# Motor-Driver-Sheet.net
KiCad netlist of a schematic drawn in Altium Designer
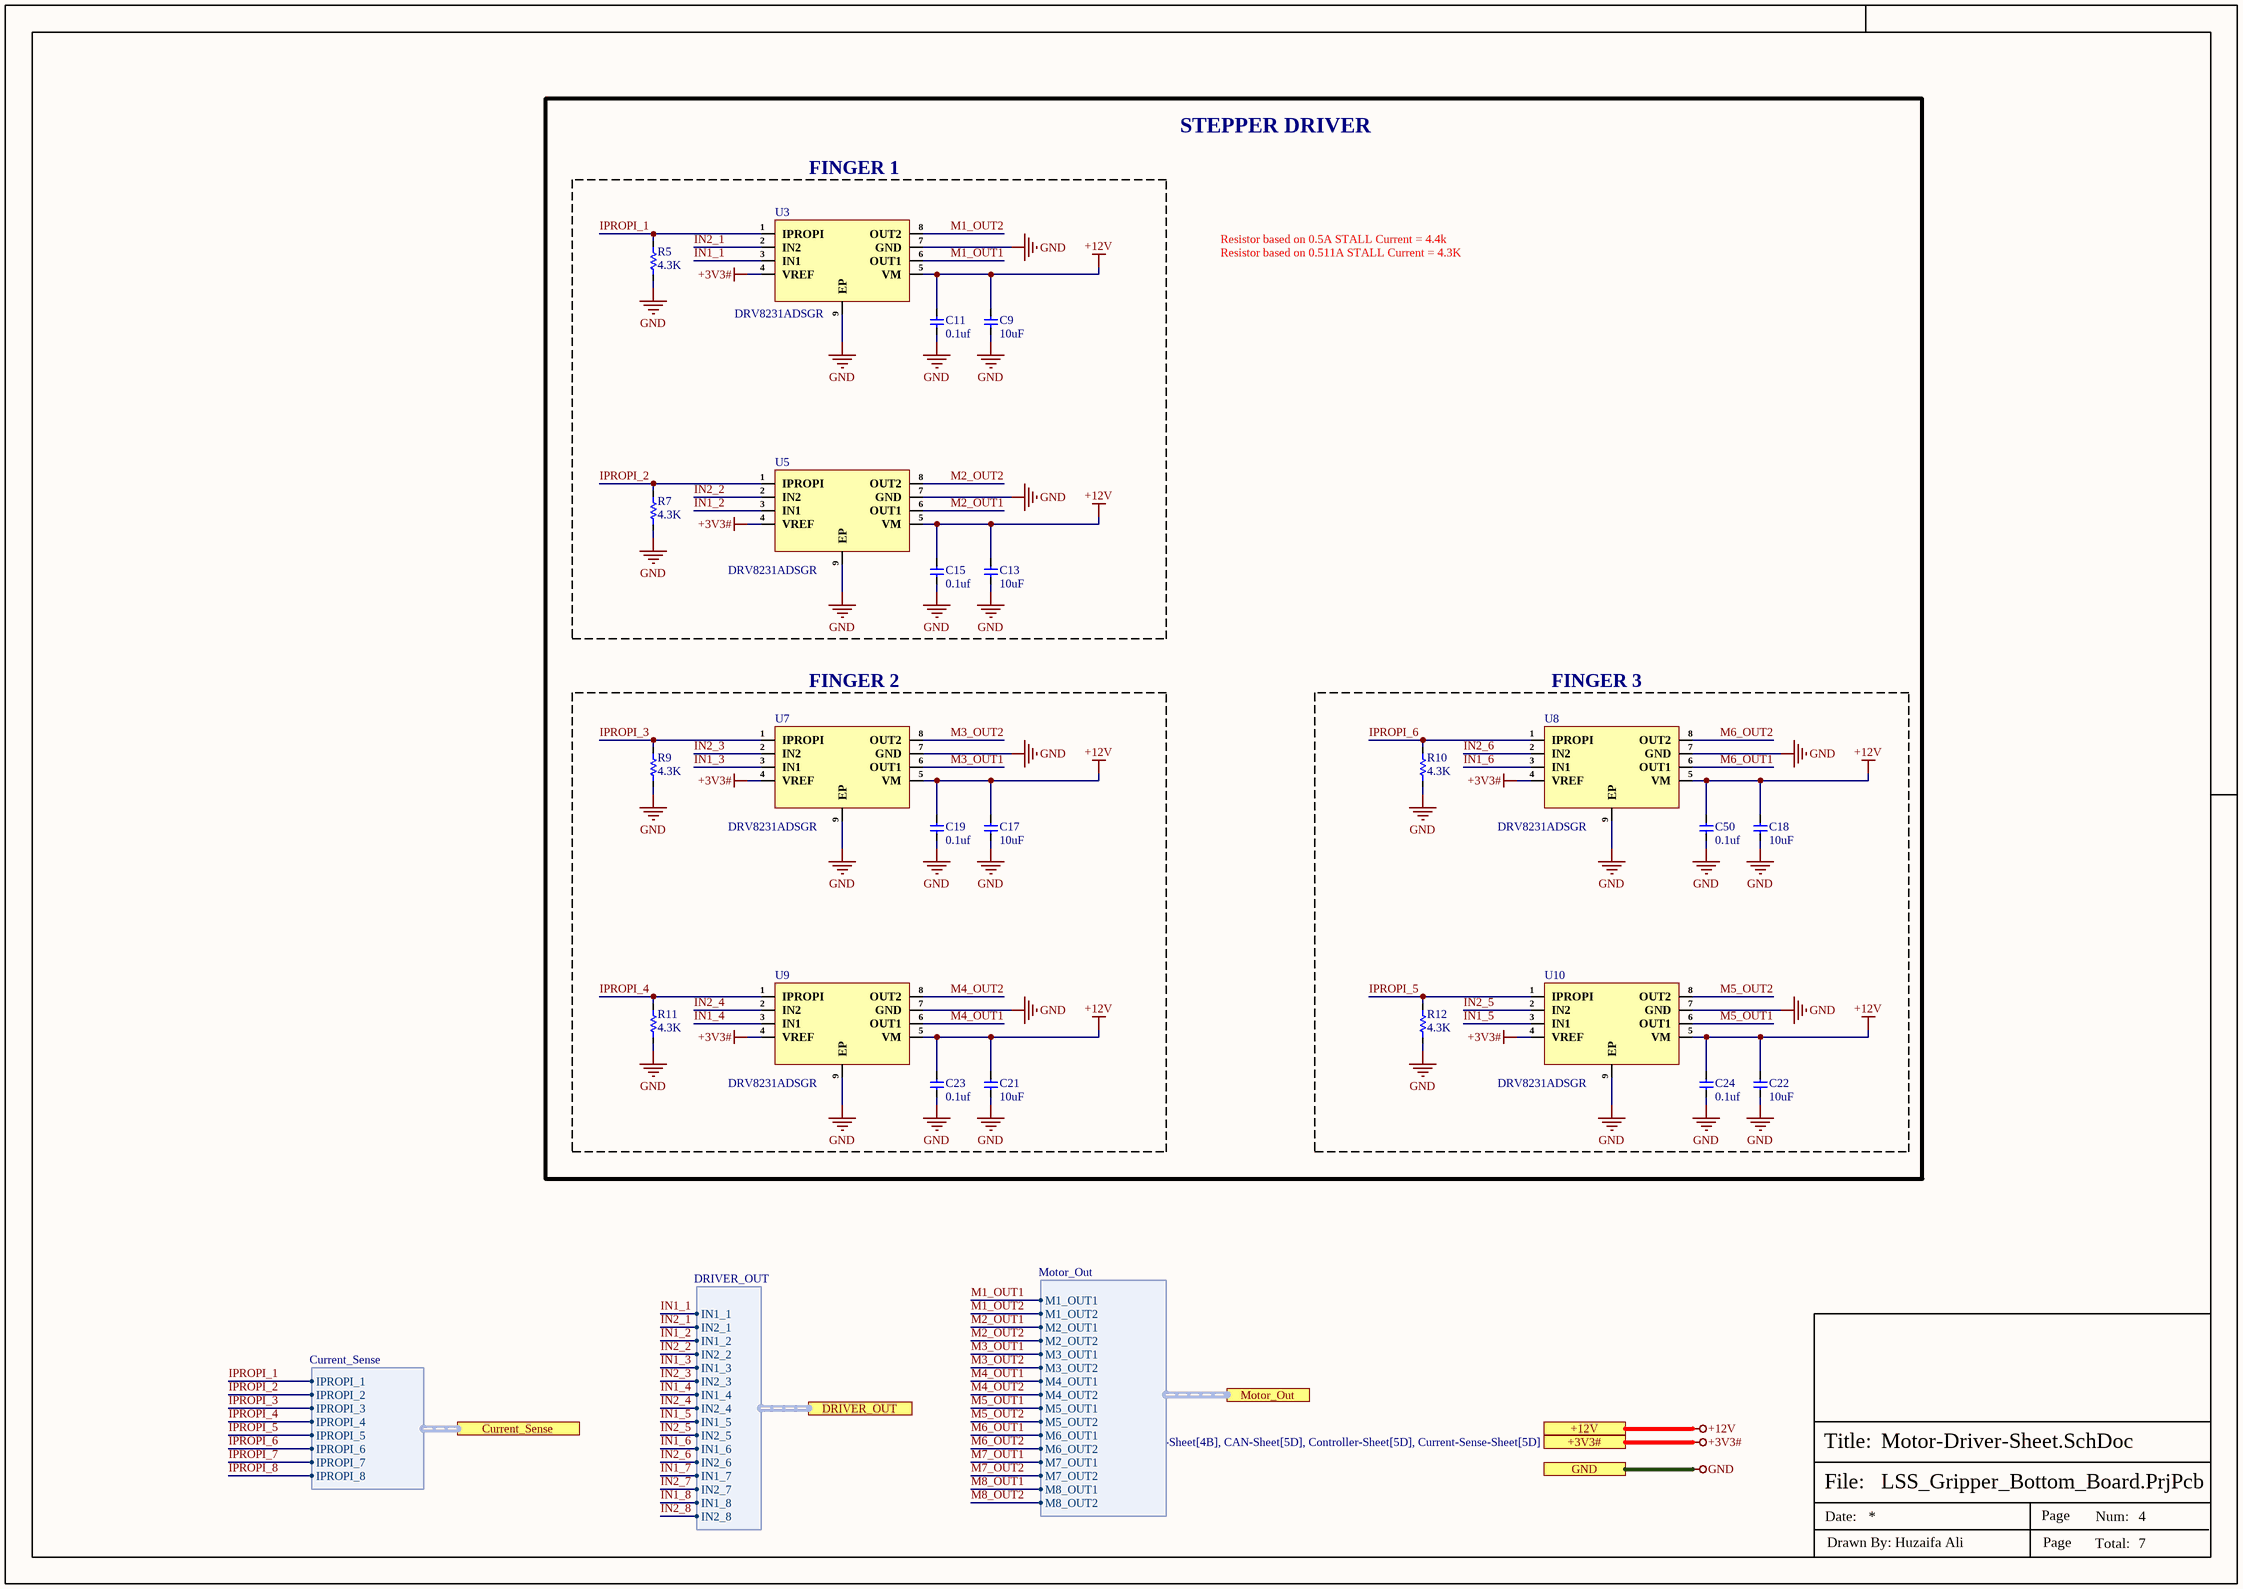
[diagram p0: Motor-Driver-Sheet.SchDoc]

(export (version "E")
  (design (tool "Eeschema 10.0.6"))
  (components
    (comp (ref "C9")
      (value "10uF")
      (footprint "Cap-0603")
      (description "CAP CER 10UF 25V X5R 0603")
      (fields
        (field (name "MANUFACTURER") "Murata")
        (field (name "MANUFACTURER PART NUMBER") "GRM188R61E106KA73D")
      )
      (libsource (lib "eSpark Libraries") (part "GRM188R61E106KA73D"))
    )
    (comp (ref "C11")
      (value "0.1uf")
      (footprint "Cap-0402")
      (description "CAP CER 0.1UF 100V X5R 0402")
      (fields
        (field (name "MANUFACTURER") "Murata")
        (field (name "MANUFACTURER PART NUMBER") "GRM155R62A104KE14D")
      )
      (libsource (lib "eSpark Libraries") (part "GRM155R62A104KE14D"))
    )
    (comp (ref "C13")
      (value "10uF")
      (footprint "Cap-0603")
      (description "CAP CER 10UF 25V X5R 0603")
      (fields
        (field (name "MANUFACTURER") "Murata")
        (field (name "MANUFACTURER PART NUMBER") "GRM188R61E106KA73D")
      )
      (libsource (lib "eSpark Libraries") (part "GRM188R61E106KA73D"))
    )
    (comp (ref "C15")
      (value "0.1uf")
      (footprint "Cap-0402")
      (description "CAP CER 0.1UF 100V X5R 0402")
      (fields
        (field (name "MANUFACTURER") "Murata")
        (field (name "MANUFACTURER PART NUMBER") "GRM155R62A104KE14D")
      )
      (libsource (lib "eSpark Libraries") (part "GRM155R62A104KE14D"))
    )
    (comp (ref "C17")
      (value "10uF")
      (footprint "Cap-0603")
      (description "CAP CER 10UF 25V X5R 0603")
      (fields
        (field (name "MANUFACTURER") "Murata")
        (field (name "MANUFACTURER PART NUMBER") "GRM188R61E106KA73D")
      )
      (libsource (lib "eSpark Libraries") (part "GRM188R61E106KA73D"))
    )
    (comp (ref "C18")
      (value "10uF")
      (footprint "Cap-0603")
      (description "CAP CER 10UF 25V X5R 0603")
      (fields
        (field (name "MANUFACTURER") "Murata")
        (field (name "MANUFACTURER PART NUMBER") "GRM188R61E106KA73D")
      )
      (libsource (lib "eSpark Libraries") (part "GRM188R61E106KA73D"))
    )
    (comp (ref "C19")
      (value "0.1uf")
      (footprint "Cap-0402")
      (description "CAP CER 0.1UF 100V X5R 0402")
      (fields
        (field (name "MANUFACTURER") "Murata")
        (field (name "MANUFACTURER PART NUMBER") "GRM155R62A104KE14D")
      )
      (libsource (lib "eSpark Libraries") (part "GRM155R62A104KE14D"))
    )
    (comp (ref "C21")
      (value "10uF")
      (footprint "Cap-0603")
      (description "CAP CER 10UF 25V X5R 0603")
      (fields
        (field (name "MANUFACTURER") "Murata")
        (field (name "MANUFACTURER PART NUMBER") "GRM188R61E106KA73D")
      )
      (libsource (lib "eSpark Libraries") (part "GRM188R61E106KA73D"))
    )
    (comp (ref "C22")
      (value "10uF")
      (footprint "Cap-0603")
      (description "CAP CER 10UF 25V X5R 0603")
      (fields
        (field (name "MANUFACTURER") "Murata")
        (field (name "MANUFACTURER PART NUMBER") "GRM188R61E106KA73D")
      )
      (libsource (lib "eSpark Libraries") (part "GRM188R61E106KA73D"))
    )
    (comp (ref "C23")
      (value "0.1uf")
      (footprint "Cap-0402")
      (description "CAP CER 0.1UF 100V X5R 0402")
      (fields
        (field (name "MANUFACTURER") "Murata")
        (field (name "MANUFACTURER PART NUMBER") "GRM155R62A104KE14D")
      )
      (libsource (lib "eSpark Libraries") (part "GRM155R62A104KE14D"))
    )
    (comp (ref "C24")
      (value "0.1uf")
      (footprint "Cap-0402")
      (description "CAP CER 0.1UF 100V X5R 0402")
      (fields
        (field (name "MANUFACTURER") "Murata")
        (field (name "MANUFACTURER PART NUMBER") "GRM155R62A104KE14D")
      )
      (libsource (lib "eSpark Libraries") (part "GRM155R62A104KE14D"))
    )
    (comp (ref "C50")
      (value "0.1uf")
      (footprint "Cap-0402")
      (description "CAP CER 0.1UF 100V X5R 0402")
      (fields
        (field (name "MANUFACTURER") "Murata")
        (field (name "MANUFACTURER PART NUMBER") "GRM155R62A104KE14D")
      )
      (libsource (lib "eSpark Libraries") (part "GRM155R62A104KE14D"))
    )
    (comp (ref "R5")
      (value "4.3K")
      (footprint "Res-0402")
      (description "62.5mW Thick Film Resistors 50V ±100ppm/℃ ±1% 4.3kΩ 0402 Chip Resistor - Surface Mount ROHS")
      (fields
        (field (name "MANUFACTURER") "Royal Electronic Factory")
        (field (name "MANUFACTURER PART NUMBER") "0402WGF4301TCE")
      )
      (libsource (lib "eSpark Libraries") (part "0402WGF4301TCE"))
    )
    (comp (ref "R7")
      (value "4.3K")
      (footprint "Res-0402")
      (description "62.5mW Thick Film Resistors 50V ±100ppm/℃ ±1% 4.3kΩ 0402 Chip Resistor - Surface Mount ROHS")
      (fields
        (field (name "MANUFACTURER") "Royal Electronic Factory")
        (field (name "MANUFACTURER PART NUMBER") "0402WGF4301TCE")
      )
      (libsource (lib "eSpark Libraries") (part "0402WGF4301TCE"))
    )
    (comp (ref "R9")
      (value "4.3K")
      (footprint "Res-0402")
      (description "62.5mW Thick Film Resistors 50V ±100ppm/℃ ±1% 4.3kΩ 0402 Chip Resistor - Surface Mount ROHS")
      (fields
        (field (name "MANUFACTURER") "Royal Electronic Factory")
        (field (name "MANUFACTURER PART NUMBER") "0402WGF4301TCE")
      )
      (libsource (lib "eSpark Libraries") (part "0402WGF4301TCE"))
    )
    (comp (ref "R10")
      (value "4.3K")
      (footprint "Res-0402")
      (description "62.5mW Thick Film Resistors 50V ±100ppm/℃ ±1% 4.3kΩ 0402 Chip Resistor - Surface Mount ROHS")
      (fields
        (field (name "MANUFACTURER") "Royal Electronic Factory")
        (field (name "MANUFACTURER PART NUMBER") "0402WGF4301TCE")
      )
      (libsource (lib "eSpark Libraries") (part "0402WGF4301TCE"))
    )
    (comp (ref "R11")
      (value "4.3K")
      (footprint "Res-0402")
      (description "62.5mW Thick Film Resistors 50V ±100ppm/℃ ±1% 4.3kΩ 0402 Chip Resistor - Surface Mount ROHS")
      (fields
        (field (name "MANUFACTURER") "Royal Electronic Factory")
        (field (name "MANUFACTURER PART NUMBER") "0402WGF4301TCE")
      )
      (libsource (lib "eSpark Libraries") (part "0402WGF4301TCE"))
    )
    (comp (ref "R12")
      (value "4.3K")
      (footprint "Res-0402")
      (description "62.5mW Thick Film Resistors 50V ±100ppm/℃ ±1% 4.3kΩ 0402 Chip Resistor - Surface Mount ROHS")
      (fields
        (field (name "MANUFACTURER") "Royal Electronic Factory")
        (field (name "MANUFACTURER PART NUMBER") "0402WGF4301TCE")
      )
      (libsource (lib "eSpark Libraries") (part "0402WGF4301TCE"))
    )
    (comp (ref "U3")
      (value "DRV8231ADSGR")
      (footprint "WSON-8(2x2)")
      (description "33V H BRIDGE MOTOR DRIVER WITH C")
      (fields (field (name "MANUFACTURER") "Texas Instruments") (field (name "LCSC PART NUMBER") "C5139865"))
      (libsource (lib "eSpark Libraries") (part "DRV8231ADSGR"))
    )
    (comp (ref "U5")
      (value "DRV8231ADSGR")
      (footprint "WSON-8(2x2)")
      (description "33V H BRIDGE MOTOR DRIVER WITH C")
      (fields (field (name "MANUFACTURER") "Texas Instruments") (field (name "LCSC PART NUMBER") "C5139865"))
      (libsource (lib "eSpark Libraries") (part "DRV8231ADSGR"))
    )
    (comp (ref "U7")
      (value "DRV8231ADSGR")
      (footprint "WSON-8(2x2)")
      (description "33V H BRIDGE MOTOR DRIVER WITH C")
      (fields (field (name "MANUFACTURER") "Texas Instruments") (field (name "LCSC PART NUMBER") "C5139865"))
      (libsource (lib "eSpark Libraries") (part "DRV8231ADSGR"))
    )
    (comp (ref "U8")
      (value "DRV8231ADSGR")
      (footprint "WSON-8(2x2)")
      (description "33V H BRIDGE MOTOR DRIVER WITH C")
      (fields (field (name "MANUFACTURER") "Texas Instruments") (field (name "LCSC PART NUMBER") "C5139865"))
      (libsource (lib "eSpark Libraries") (part "DRV8231ADSGR"))
    )
    (comp (ref "U9")
      (value "DRV8231ADSGR")
      (footprint "WSON-8(2x2)")
      (description "33V H BRIDGE MOTOR DRIVER WITH C")
      (fields (field (name "MANUFACTURER") "Texas Instruments") (field (name "LCSC PART NUMBER") "C5139865"))
      (libsource (lib "eSpark Libraries") (part "DRV8231ADSGR"))
    )
    (comp (ref "U10")
      (value "DRV8231ADSGR")
      (footprint "WSON-8(2x2)")
      (description "33V H BRIDGE MOTOR DRIVER WITH C")
      (fields (field (name "MANUFACTURER") "Texas Instruments") (field (name "LCSC PART NUMBER") "C5139865"))
      (libsource (lib "eSpark Libraries") (part "DRV8231ADSGR"))
    )
  )
  (nets
    (net (code "4") (name "+3V3#") (class "Default")
      (node (ref "U10") (pin "4") (pinfunction "VREF_4") (pintype "passive"))
      (node (ref "U3") (pin "4") (pinfunction "VREF_4") (pintype "passive"))
      (node (ref "U5") (pin "4") (pinfunction "VREF_4") (pintype "passive"))
      (node (ref "U7") (pin "4") (pinfunction "VREF_4") (pintype "passive"))
      (node (ref "U8") (pin "4") (pinfunction "VREF_4") (pintype "passive"))
      (node (ref "U9") (pin "4") (pinfunction "VREF_4") (pintype "passive"))
    )
    (net (code "5") (name "+12V") (class "Default")
      (node (ref "C11") (pin "2") (pinfunction "2_2") (pintype "passive"))
      (node (ref "C13") (pin "2") (pinfunction "2_2") (pintype "passive"))
      (node (ref "C15") (pin "2") (pinfunction "2_2") (pintype "passive"))
      (node (ref "C17") (pin "2") (pinfunction "2_2") (pintype "passive"))
      (node (ref "C18") (pin "2") (pinfunction "2_2") (pintype "passive"))
      (node (ref "C19") (pin "2") (pinfunction "2_2") (pintype "passive"))
      (node (ref "C21") (pin "2") (pinfunction "2_2") (pintype "passive"))
      (node (ref "C22") (pin "2") (pinfunction "2_2") (pintype "passive"))
      (node (ref "C23") (pin "2") (pinfunction "2_2") (pintype "passive"))
      (node (ref "C24") (pin "2") (pinfunction "2_2") (pintype "passive"))
      (node (ref "C50") (pin "2") (pinfunction "2_2") (pintype "passive"))
      (node (ref "C9") (pin "2") (pinfunction "2_2") (pintype "passive"))
      (node (ref "U10") (pin "5") (pinfunction "VM_5") (pintype "passive"))
      (node (ref "U3") (pin "5") (pinfunction "VM_5") (pintype "passive"))
      (node (ref "U5") (pin "5") (pinfunction "VM_5") (pintype "passive"))
      (node (ref "U7") (pin "5") (pinfunction "VM_5") (pintype "passive"))
      (node (ref "U8") (pin "5") (pinfunction "VM_5") (pintype "passive"))
      (node (ref "U9") (pin "5") (pinfunction "VM_5") (pintype "passive"))
    )
    (net (code "6") (name "/IN1_1") (class "Default")
      (node (ref "U3") (pin "3") (pinfunction "IN1_3") (pintype "passive"))
    )
    (net (code "7") (name "/IN1_2") (class "Default")
      (node (ref "U5") (pin "3") (pinfunction "IN1_3") (pintype "passive"))
    )
    (net (code "8") (name "/IN1_3") (class "Default")
      (node (ref "U7") (pin "3") (pinfunction "IN1_3") (pintype "passive"))
    )
    (net (code "9") (name "/IN1_4") (class "Default")
      (node (ref "U9") (pin "3") (pinfunction "IN1_3") (pintype "passive"))
    )
    (net (code "10") (name "/IN1_5") (class "Default")
      (node (ref "U10") (pin "3") (pinfunction "IN1_3") (pintype "passive"))
    )
    (net (code "11") (name "/IN1_6") (class "Default")
      (node (ref "U8") (pin "3") (pinfunction "IN1_3") (pintype "passive"))
    )
    (net (code "14") (name "/IN2_1") (class "Default")
      (node (ref "U3") (pin "2") (pinfunction "IN2_2") (pintype "passive"))
    )
    (net (code "15") (name "/IN2_2") (class "Default")
      (node (ref "U5") (pin "2") (pinfunction "IN2_2") (pintype "passive"))
    )
    (net (code "16") (name "/IN2_3") (class "Default")
      (node (ref "U7") (pin "2") (pinfunction "IN2_2") (pintype "passive"))
    )
    (net (code "17") (name "/IN2_4") (class "Default")
      (node (ref "U9") (pin "2") (pinfunction "IN2_2") (pintype "passive"))
    )
    (net (code "18") (name "/IN2_5") (class "Default")
      (node (ref "U10") (pin "2") (pinfunction "IN2_2") (pintype "passive"))
    )
    (net (code "19") (name "/IN2_6") (class "Default")
      (node (ref "U8") (pin "2") (pinfunction "IN2_2") (pintype "passive"))
    )
    (net (code "22") (name "/IPROPI_1") (class "Default")
      (node (ref "R5") (pin "2") (pinfunction "2_2") (pintype "passive"))
      (node (ref "U3") (pin "1") (pinfunction "IPROPI_1") (pintype "passive"))
    )
    (net (code "23") (name "/IPROPI_2") (class "Default")
      (node (ref "R7") (pin "2") (pinfunction "2_2") (pintype "passive"))
      (node (ref "U5") (pin "1") (pinfunction "IPROPI_1") (pintype "passive"))
    )
    (net (code "24") (name "/IPROPI_3") (class "Default")
      (node (ref "R9") (pin "2") (pinfunction "2_2") (pintype "passive"))
      (node (ref "U7") (pin "1") (pinfunction "IPROPI_1") (pintype "passive"))
    )
    (net (code "25") (name "/IPROPI_4") (class "Default")
      (node (ref "R11") (pin "2") (pinfunction "2_2") (pintype "passive"))
      (node (ref "U9") (pin "1") (pinfunction "IPROPI_1") (pintype "passive"))
    )
    (net (code "26") (name "/IPROPI_5") (class "Default")
      (node (ref "R12") (pin "2") (pinfunction "2_2") (pintype "passive"))
      (node (ref "U10") (pin "1") (pinfunction "IPROPI_1") (pintype "passive"))
    )
    (net (code "27") (name "/IPROPI_6") (class "Default")
      (node (ref "R10") (pin "2") (pinfunction "2_2") (pintype "passive"))
      (node (ref "U8") (pin "1") (pinfunction "IPROPI_1") (pintype "passive"))
    )
    (net (code "30") (name "/M1_OUT1") (class "Default")
      (node (ref "U3") (pin "6") (pinfunction "OUT1_6") (pintype "passive"))
    )
    (net (code "31") (name "/M1_OUT2") (class "Default")
      (node (ref "U3") (pin "8") (pinfunction "OUT2_8") (pintype "passive"))
    )
    (net (code "32") (name "/M2_OUT1") (class "Default")
      (node (ref "U5") (pin "6") (pinfunction "OUT1_6") (pintype "passive"))
    )
    (net (code "33") (name "/M2_OUT2") (class "Default")
      (node (ref "U5") (pin "8") (pinfunction "OUT2_8") (pintype "passive"))
    )
    (net (code "34") (name "/M3_OUT1") (class "Default")
      (node (ref "U7") (pin "6") (pinfunction "OUT1_6") (pintype "passive"))
    )
    (net (code "35") (name "/M3_OUT2") (class "Default")
      (node (ref "U7") (pin "8") (pinfunction "OUT2_8") (pintype "passive"))
    )
    (net (code "36") (name "/M4_OUT1") (class "Default")
      (node (ref "U9") (pin "6") (pinfunction "OUT1_6") (pintype "passive"))
    )
    (net (code "37") (name "/M4_OUT2") (class "Default")
      (node (ref "U9") (pin "8") (pinfunction "OUT2_8") (pintype "passive"))
    )
    (net (code "38") (name "/M5_OUT1") (class "Default")
      (node (ref "U10") (pin "6") (pinfunction "OUT1_6") (pintype "passive"))
    )
    (net (code "39") (name "/M5_OUT2") (class "Default")
      (node (ref "U10") (pin "8") (pinfunction "OUT2_8") (pintype "passive"))
    )
    (net (code "40") (name "/M6_OUT1") (class "Default")
      (node (ref "U8") (pin "6") (pinfunction "OUT1_6") (pintype "passive"))
    )
    (net (code "41") (name "/M6_OUT2") (class "Default")
      (node (ref "U8") (pin "8") (pinfunction "OUT2_8") (pintype "passive"))
    )
    (net (code "49") (name "GND") (class "Default")
      (node (ref "C11") (pin "1") (pinfunction "1_1") (pintype "passive"))
      (node (ref "C13") (pin "1") (pinfunction "1_1") (pintype "passive"))
      (node (ref "C15") (pin "1") (pinfunction "1_1") (pintype "passive"))
      (node (ref "C17") (pin "1") (pinfunction "1_1") (pintype "passive"))
      (node (ref "C18") (pin "1") (pinfunction "1_1") (pintype "passive"))
      (node (ref "C19") (pin "1") (pinfunction "1_1") (pintype "passive"))
      (node (ref "C21") (pin "1") (pinfunction "1_1") (pintype "passive"))
      (node (ref "C22") (pin "1") (pinfunction "1_1") (pintype "passive"))
      (node (ref "C23") (pin "1") (pinfunction "1_1") (pintype "passive"))
      (node (ref "C24") (pin "1") (pinfunction "1_1") (pintype "passive"))
      (node (ref "C50") (pin "1") (pinfunction "1_1") (pintype "passive"))
      (node (ref "C9") (pin "1") (pinfunction "1_1") (pintype "passive"))
      (node (ref "R10") (pin "1") (pinfunction "1_1") (pintype "passive"))
      (node (ref "R11") (pin "1") (pinfunction "1_1") (pintype "passive"))
      (node (ref "R12") (pin "1") (pinfunction "1_1") (pintype "passive"))
      (node (ref "R5") (pin "1") (pinfunction "1_1") (pintype "passive"))
      (node (ref "R7") (pin "1") (pinfunction "1_1") (pintype "passive"))
      (node (ref "R9") (pin "1") (pinfunction "1_1") (pintype "passive"))
      (node (ref "U10") (pin "7") (pinfunction "GND_7") (pintype "passive"))
      (node (ref "U10") (pin "9") (pinfunction "EP_9") (pintype "passive"))
      (node (ref "U3") (pin "7") (pinfunction "GND_7") (pintype "passive"))
      (node (ref "U3") (pin "9") (pinfunction "EP_9") (pintype "passive"))
      (node (ref "U5") (pin "7") (pinfunction "GND_7") (pintype "passive"))
      (node (ref "U5") (pin "9") (pinfunction "EP_9") (pintype "passive"))
      (node (ref "U7") (pin "7") (pinfunction "GND_7") (pintype "passive"))
      (node (ref "U7") (pin "9") (pinfunction "EP_9") (pintype "passive"))
      (node (ref "U8") (pin "7") (pinfunction "GND_7") (pintype "passive"))
      (node (ref "U8") (pin "9") (pinfunction "EP_9") (pintype "passive"))
      (node (ref "U9") (pin "7") (pinfunction "GND_7") (pintype "passive"))
      (node (ref "U9") (pin "9") (pinfunction "EP_9") (pintype "passive"))
    )
  )
)
